# OLED.net
KiCad netlist of a schematic drawn in Altium Designer
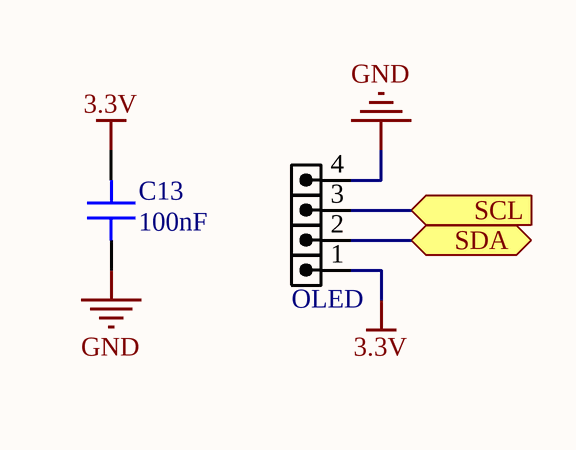
[diagram p0: OLED.SchDoc]

(export (version "E")
  (design (tool "Eeschema 10.0.6"))
  (components
    (comp (ref "C13")
      (value "100nF")
      (footprint "CAP 0603_1608")
      (description "SMT Capacitor")
      (libsource (lib "Capacitor") (part "Cap 0603"))
    )
    (comp (ref "OLED")
      (value "HDR4")
      (footprint "HDR1SE_M_1X4")
      (description "HEADER, 1mm pitch, test, SMD")
      (libsource (lib "Conn Header") (part "HDRTST_1X4"))
    )
  )
  (nets
    (net (code "1") (name "/SCL") (class "Default")
      (node (ref "OLED") (pin "3") (pinfunction "3_3") (pintype "passive"))
    )
    (net (code "2") (name "/SDA") (class "Default")
      (node (ref "OLED") (pin "2") (pinfunction "2_2") (pintype "passive"))
    )
    (net (code "3") (name "3.3V") (class "Default")
      (node (ref "C13") (pin "2") (pinfunction "2_2") (pintype "passive"))
      (node (ref "OLED") (pin "1") (pinfunction "1_1") (pintype "passive"))
    )
    (net (code "4") (name "GND") (class "Default")
      (node (ref "C13") (pin "1") (pinfunction "1_1") (pintype "passive"))
      (node (ref "OLED") (pin "4") (pinfunction "4_4") (pintype "passive"))
    )
  )
)
